# asset-tracker-v002.net
KiCad netlist of a schematic drawn in EAGLE
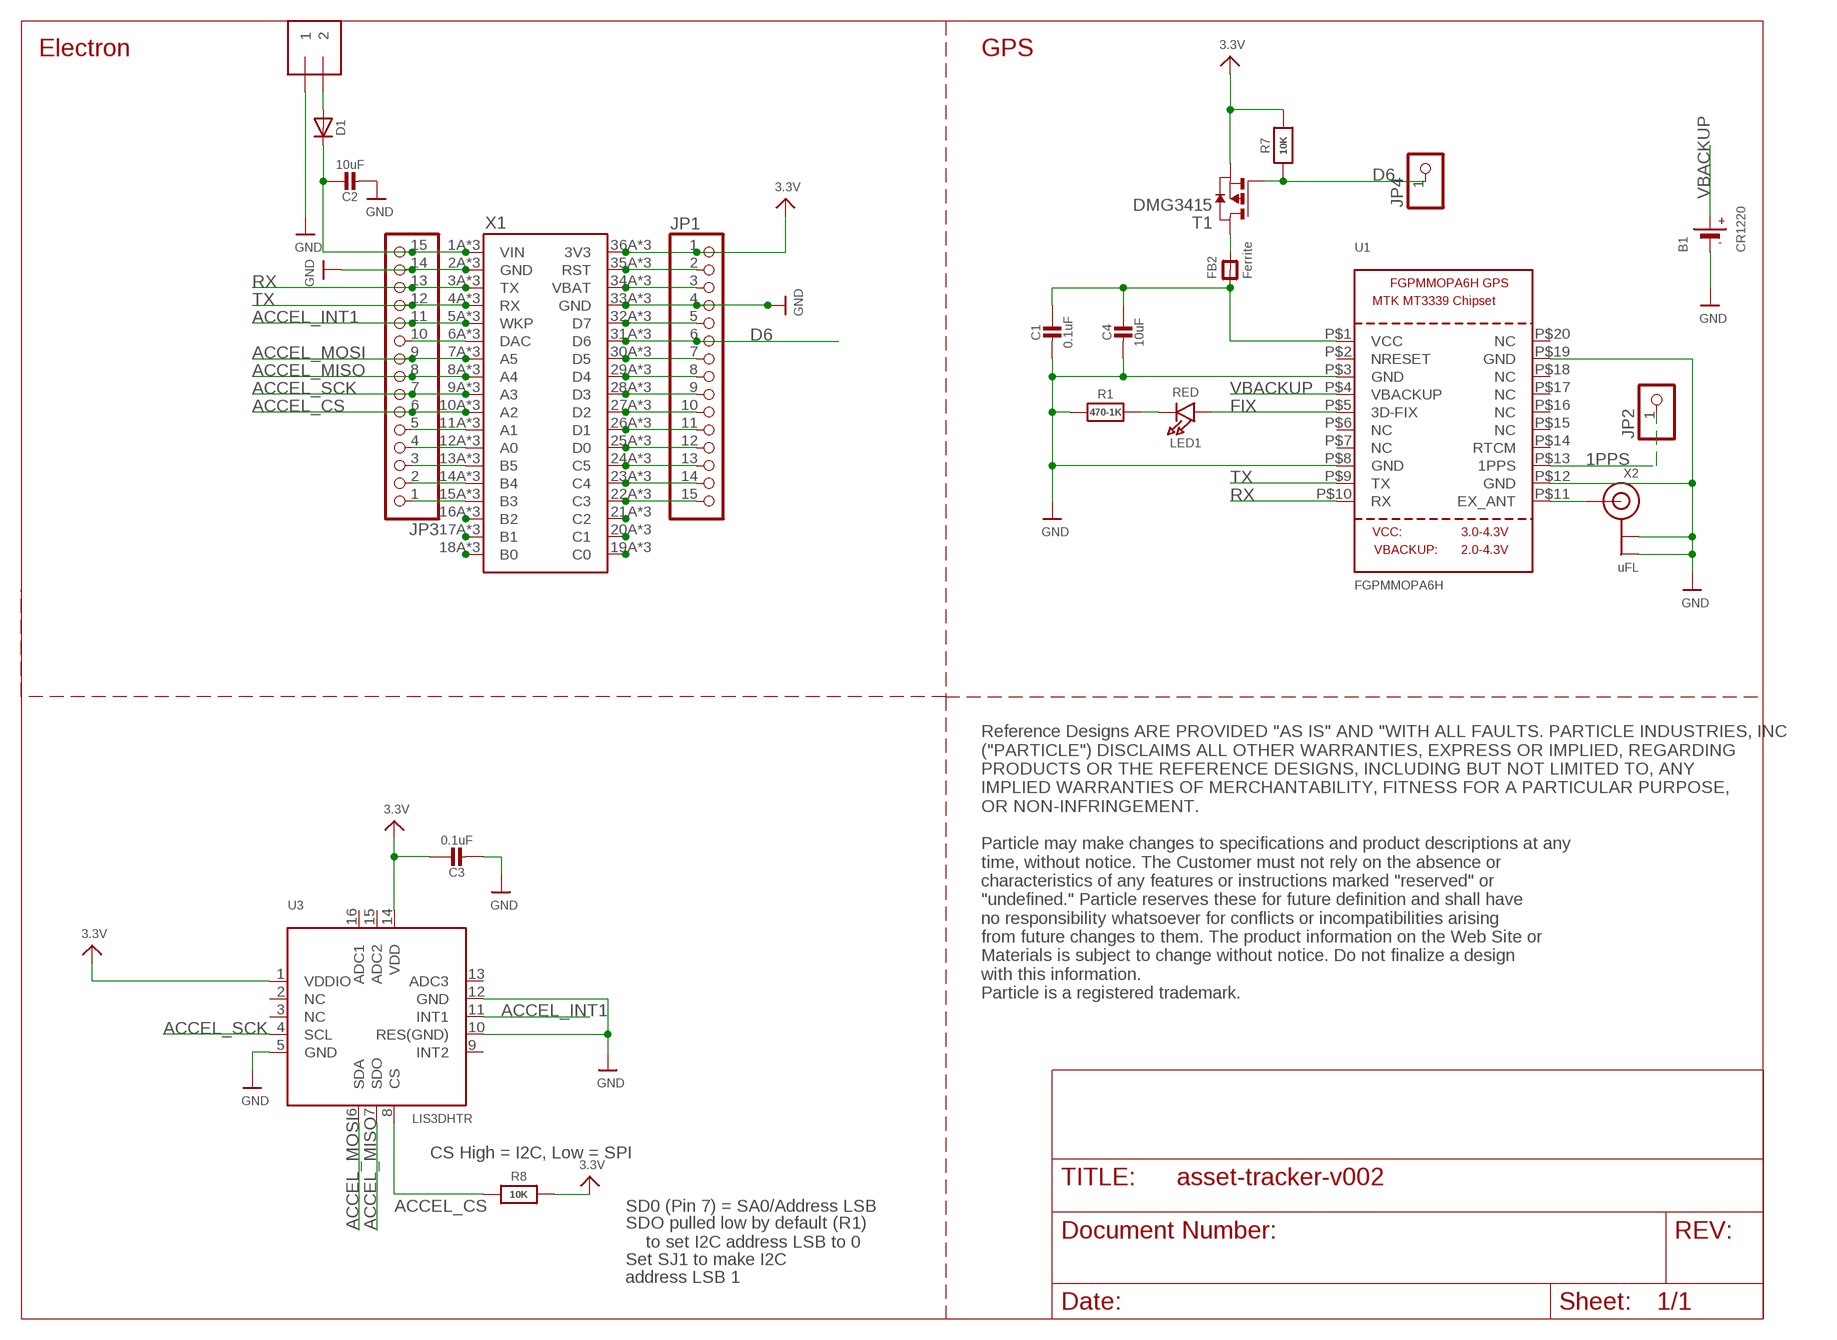
[diagram p0: schematic, sheet 1]

(export (version "E")
  (design (tool "Eeschema 10.0.6"))
  (components
    (comp (ref "B1")
      (value "CR1220")
      (footprint "eagle-import:CR1220")
      (libsource (lib "eagle-import") (part "BATTERYCR1220_SMT"))
    )
    (comp (ref "C1")
      (value "0.1uF")
      (footprint "eagle-import:0805-NO@1")
      (libsource (lib "eagle-import") (part "CAP_CERAMIC0805-NOOUTLINE"))
    )
    (comp (ref "C2")
      (value "10uF")
      (footprint "eagle-import:0805-NO@1")
      (libsource (lib "eagle-import") (part "CAP_CERAMIC0805-NOOUTLINE"))
    )
    (comp (ref "C3")
      (value "0.1uF")
      (footprint "eagle-import:0805_10MGAP")
      (libsource (lib "eagle-import") (part "CAP_CERAMIC0805_10MGAP"))
    )
    (comp (ref "C4")
      (value "10uF")
      (footprint "eagle-import:0805-NO@1")
      (libsource (lib "eagle-import") (part "CAP_CERAMIC0805-NOOUTLINE"))
    )
    (comp (ref "D1")
      (value "DIODESMA")
      (footprint "eagle-import:SMADIODE")
      (libsource (lib "eagle-import") (part "DIODESMA"))
    )
    (comp (ref "FB2")
      (value "Ferrite")
      (footprint "eagle-import:0805-NO@1")
      (libsource (lib "eagle-import") (part "FERRITE-0805NO"))
    )
    (comp (ref "J1")
      (value "1X2-3.5MM")
      (footprint "eagle-import:1X2-3.5MM")
      (libsource (lib "eagle-import") (part "1X2-3.5MM"))
    )
    (comp (ref "JP1")
      (value "HEADER-1X15")
      (footprint "eagle-import:1X15_ROUND_70")
      (libsource (lib "eagle-import") (part "HEADER-1X15"))
    )
    (comp (ref "JP2")
      (value "HEADER-1X1ROUND")
      (footprint "eagle-import:1X01_ROUND")
      (libsource (lib "eagle-import") (part "HEADER-1X1ROUND"))
    )
    (comp (ref "JP3")
      (value "HEADER-1X15")
      (footprint "eagle-import:1X15_ROUND_70")
      (libsource (lib "eagle-import") (part "HEADER-1X15"))
    )
    (comp (ref "JP4")
      (value "HEADER-1X1ROUND")
      (footprint "eagle-import:1X01_ROUND")
      (libsource (lib "eagle-import") (part "HEADER-1X1ROUND"))
    )
    (comp (ref "LED1")
      (value "RED")
      (footprint "eagle-import:CHIPLED_0805_NOOUTLINE")
      (libsource (lib "eagle-import") (part "LED0805_NOOUTLINE"))
    )
    (comp (ref "R1")
      (value "470-1K")
      (footprint "eagle-import:0805-NO")
      (libsource (lib "eagle-import") (part "RESISTOR0805_NOOUTLINE"))
    )
    (comp (ref "R7")
      (value "10K")
      (footprint "eagle-import:0805-NO")
      (libsource (lib "eagle-import") (part "RESISTOR0805_NOOUTLINE"))
    )
    (comp (ref "R8")
      (value "10K")
      (footprint "eagle-import:0805-NO")
      (libsource (lib "eagle-import") (part "RESISTOR0805_NOOUTLINE"))
    )
    (comp (ref "T1")
      (value "DMG3415")
      (footprint "eagle-import:SOT-23")
      (libsource (lib "eagle-import") (part "PMOSSOT23"))
    )
    (comp (ref "U1")
      (value "FGPMMOPA6H")
      (footprint "eagle-import:FGPMMOPA6H")
      (libsource (lib "eagle-import") (part "GPS_FGPMMOPA6H"))
    )
    (comp (ref "U3")
      (value "LIS3DHTR")
      (footprint "eagle-import:LGA16_3X3MM")
      (libsource (lib "eagle-import") (part "ACCEL_LIS3DHTR"))
    )
    (comp (ref "X1")
      (value "ELECTRON")
      (footprint "eagle-import:ELECTRON_SMT")
      (libsource (lib "eagle-import") (part "ELECTRON_SMT"))
    )
    (comp (ref "X2")
      (value "uFL")
      (footprint "eagle-import:U.FL")
      (libsource (lib "eagle-import") (part "ANTENNA_U.FL"))
    )
  )
  (nets
    (net (code "1") (name "/1PPS") (class "Default")
      (node (ref "JP2") (pin "1") (pinfunction "1_1") (pintype "passive"))
      (node (ref "U1") (pin "P$13") (pinfunction "1PPS_P$13") (pintype "bidirectional"))
    )
    (net (code "2") (name "/ACCEL_CS") (class "Default")
      (node (ref "JP3") (pin "6") (pinfunction "6_6") (pintype "passive"))
      (node (ref "R8") (pin "1") (pinfunction "1_1") (pintype "passive"))
      (node (ref "U3") (pin "8") (pinfunction "CS_8") (pintype "input"))
      (node (ref "X1") (pin "10A") (pinfunction "A2_10A") (pintype "bidirectional"))
      (node (ref "X1") (pin "10B") (pinfunction "A2_10B") (pintype "bidirectional"))
      (node (ref "X1") (pin "10C") (pinfunction "A2_10C") (pintype "bidirectional"))
    )
    (net (code "3") (name "/ACCEL_INT1") (class "Default")
      (node (ref "JP3") (pin "11") (pinfunction "11_11") (pintype "passive"))
      (node (ref "U3") (pin "11") (pinfunction "INT1_11") (pintype "output"))
      (node (ref "X1") (pin "5A") (pinfunction "WKP_5A") (pintype "bidirectional"))
      (node (ref "X1") (pin "5B") (pinfunction "WKP_5B") (pintype "bidirectional"))
      (node (ref "X1") (pin "5C") (pinfunction "WKP_5C") (pintype "bidirectional"))
    )
    (net (code "4") (name "/ACCEL_MISO") (class "Default")
      (node (ref "JP3") (pin "8") (pinfunction "8_8") (pintype "passive"))
      (node (ref "U3") (pin "7") (pinfunction "SDO_7") (pintype "bidirectional"))
      (node (ref "X1") (pin "8A") (pinfunction "A4_8A") (pintype "bidirectional"))
      (node (ref "X1") (pin "8B") (pinfunction "A4_8B") (pintype "bidirectional"))
      (node (ref "X1") (pin "8C") (pinfunction "A4_8C") (pintype "bidirectional"))
    )
    (net (code "5") (name "/ACCEL_MOSI") (class "Default")
      (node (ref "JP3") (pin "9") (pinfunction "9_9") (pintype "passive"))
      (node (ref "U3") (pin "6") (pinfunction "SDA_6") (pintype "bidirectional"))
      (node (ref "X1") (pin "7A") (pinfunction "A5_7A") (pintype "bidirectional"))
      (node (ref "X1") (pin "7B") (pinfunction "A5_7B") (pintype "bidirectional"))
      (node (ref "X1") (pin "7C") (pinfunction "A5_7C") (pintype "bidirectional"))
    )
    (net (code "6") (name "/ACCEL_SCK") (class "Default")
      (node (ref "JP3") (pin "7") (pinfunction "7_7") (pintype "passive"))
      (node (ref "U3") (pin "4") (pinfunction "SCL_4") (pintype "bidirectional"))
      (node (ref "X1") (pin "9A") (pinfunction "A3_9A") (pintype "bidirectional"))
      (node (ref "X1") (pin "9B") (pinfunction "A3_9B") (pintype "bidirectional"))
      (node (ref "X1") (pin "9C") (pinfunction "A3_9C") (pintype "bidirectional"))
    )
    (net (code "7") (name "/D6") (class "Default")
      (node (ref "JP1") (pin "6") (pinfunction "6_6") (pintype "passive"))
      (node (ref "JP4") (pin "1") (pinfunction "1_1") (pintype "passive"))
      (node (ref "R7") (pin "1") (pinfunction "1_1") (pintype "passive"))
      (node (ref "T1") (pin "3") (pinfunction "G_3") (pintype "passive"))
      (node (ref "X1") (pin "31A") (pinfunction "D6_31A") (pintype "bidirectional"))
      (node (ref "X1") (pin "31B") (pinfunction "D6_31B") (pintype "bidirectional"))
      (node (ref "X1") (pin "31C") (pinfunction "D6_31C") (pintype "bidirectional"))
    )
    (net (code "8") (name "/FIX") (class "Default")
      (node (ref "LED1") (pin "A") (pinfunction "A_A") (pintype "passive"))
      (node (ref "U1") (pin "P$5") (pinfunction "3D-FIX_P$5") (pintype "bidirectional"))
    )
    (net (code "9") (name "/RX") (class "Default")
      (node (ref "JP3") (pin "13") (pinfunction "13_13") (pintype "passive"))
      (node (ref "U1") (pin "P$10") (pinfunction "RX_P$10") (pintype "bidirectional"))
      (node (ref "X1") (pin "3A") (pinfunction "TX_3A") (pintype "bidirectional"))
      (node (ref "X1") (pin "3B") (pinfunction "TX_3B") (pintype "bidirectional"))
      (node (ref "X1") (pin "3C") (pinfunction "TX_3C") (pintype "bidirectional"))
    )
    (net (code "10") (name "/TX") (class "Default")
      (node (ref "JP3") (pin "12") (pinfunction "12_12") (pintype "passive"))
      (node (ref "U1") (pin "P$9") (pinfunction "TX_P$9") (pintype "bidirectional"))
      (node (ref "X1") (pin "4A") (pinfunction "RX_4A") (pintype "bidirectional"))
      (node (ref "X1") (pin "4B") (pinfunction "RX_4B") (pintype "bidirectional"))
      (node (ref "X1") (pin "4C") (pinfunction "RX_4C") (pintype "bidirectional"))
    )
    (net (code "11") (name "/VBACKUP") (class "Default")
      (node (ref "B1") (pin "+$1") (pinfunction "+_+$1") (pintype "passive"))
      (node (ref "U1") (pin "P$4") (pinfunction "VBACKUP_P$4") (pintype "bidirectional"))
    )
    (net (code "12") (name "3.3V") (class "Default")
      (node (ref "C3") (pin "1") (pinfunction "1_1") (pintype "passive"))
      (node (ref "JP1") (pin "1") (pinfunction "1_1") (pintype "passive"))
      (node (ref "R7") (pin "2") (pinfunction "2_2") (pintype "passive"))
      (node (ref "R8") (pin "2") (pinfunction "2_2") (pintype "passive"))
      (node (ref "T1") (pin "2") (pinfunction "S_2") (pintype "passive"))
      (node (ref "U3") (pin "1") (pinfunction "VDDIO_1") (pintype "power_in"))
      (node (ref "U3") (pin "14") (pinfunction "VDD_14") (pintype "power_in"))
      (node (ref "X1") (pin "36A") (pinfunction "3V3_36A") (pintype "power_in"))
      (node (ref "X1") (pin "36B") (pinfunction "3V3_36B") (pintype "power_in"))
      (node (ref "X1") (pin "36C") (pinfunction "3V3_36C") (pintype "power_in"))
    )
    (net (code "13") (name "GND") (class "Default")
      (node (ref "B1") (pin "-") (pinfunction "-_-") (pintype "passive"))
      (node (ref "C1") (pin "2") (pinfunction "2_2") (pintype "passive"))
      (node (ref "C2") (pin "2") (pinfunction "2_2") (pintype "passive"))
      (node (ref "C3") (pin "2") (pinfunction "2_2") (pintype "passive"))
      (node (ref "C4") (pin "2") (pinfunction "2_2") (pintype "passive"))
      (node (ref "J1") (pin "1") (pinfunction "1_1") (pintype "passive"))
      (node (ref "JP1") (pin "4") (pinfunction "4_4") (pintype "passive"))
      (node (ref "JP3") (pin "14") (pinfunction "14_14") (pintype "passive"))
      (node (ref "R1") (pin "1") (pinfunction "1_1") (pintype "passive"))
      (node (ref "U1") (pin "P$12") (pinfunction "GND_P$12") (pintype "bidirectional"))
      (node (ref "U1") (pin "P$19") (pinfunction "GND_P$19") (pintype "bidirectional"))
      (node (ref "U1") (pin "P$3") (pinfunction "GND_P$3") (pintype "bidirectional"))
      (node (ref "U1") (pin "P$8") (pinfunction "GND_P$8") (pintype "bidirectional"))
      (node (ref "U3") (pin "10") (pinfunction "RES(GND)_10") (pintype "bidirectional"))
      (node (ref "U3") (pin "12") (pinfunction "GND_12") (pintype "power_in"))
      (node (ref "U3") (pin "5") (pinfunction "GND_5") (pintype "power_in"))
      (node (ref "X1") (pin "2A") (pinfunction "GND_2A") (pintype "power_in"))
      (node (ref "X1") (pin "2B") (pinfunction "GND_2B") (pintype "power_in"))
      (node (ref "X1") (pin "2C") (pinfunction "GND_2C") (pintype "power_in"))
      (node (ref "X1") (pin "33A") (pinfunction "GND_33A") (pintype "power_in"))
      (node (ref "X1") (pin "33B") (pinfunction "GND_33B") (pintype "power_in"))
      (node (ref "X1") (pin "33C") (pinfunction "GND_33C") (pintype "power_in"))
      (node (ref "X2") (pin "1") (pinfunction "GND_1") (pintype "passive"))
      (node (ref "X2") (pin "2") (pinfunction "GND_2") (pintype "passive"))
    )
    (net (code "14") (name "Net-(C2-Pad1)") (class "Default")
      (node (ref "C2") (pin "1") (pinfunction "1_1") (pintype "passive"))
      (node (ref "D1") (pin "C") (pinfunction "C_C") (pintype "passive"))
      (node (ref "JP3") (pin "15") (pinfunction "15_15") (pintype "passive"))
      (node (ref "X1") (pin "1A") (pinfunction "VIN_1A") (pintype "power_in"))
      (node (ref "X1") (pin "1B") (pinfunction "VIN_1B") (pintype "power_in"))
      (node (ref "X1") (pin "1C") (pinfunction "VIN_1C") (pintype "power_in"))
    )
    (net (code "15") (name "Net-(D1-PadA)") (class "Default")
      (node (ref "D1") (pin "A") (pinfunction "A_A") (pintype "passive"))
      (node (ref "J1") (pin "2") (pinfunction "2_2") (pintype "passive"))
    )
    (net (code "16") (name "Net-(FB2-P$1)") (class "Default")
      (node (ref "C1") (pin "1") (pinfunction "1_1") (pintype "passive"))
      (node (ref "C4") (pin "1") (pinfunction "1_1") (pintype "passive"))
      (node (ref "FB2") (pin "1") (pinfunction "P$1_1") (pintype "passive"))
      (node (ref "U1") (pin "P$1") (pinfunction "VCC_P$1") (pintype "bidirectional"))
    )
    (net (code "17") (name "Net-(FB2-P$2)") (class "Default")
      (node (ref "FB2") (pin "2") (pinfunction "P$2_2") (pintype "passive"))
      (node (ref "T1") (pin "1") (pinfunction "D_1") (pintype "passive"))
    )
    (net (code "18") (name "Net-(JP1-Pad2)") (class "Default")
      (node (ref "JP1") (pin "2") (pinfunction "2_2") (pintype "passive"))
      (node (ref "X1") (pin "35A") (pinfunction "RST_35A") (pintype "bidirectional"))
      (node (ref "X1") (pin "35B") (pinfunction "RST_35B") (pintype "bidirectional"))
      (node (ref "X1") (pin "35C") (pinfunction "RST_35C") (pintype "bidirectional"))
    )
    (net (code "19") (name "Net-(JP1-Pad3)") (class "Default")
      (node (ref "JP1") (pin "3") (pinfunction "3_3") (pintype "passive"))
      (node (ref "X1") (pin "34A") (pinfunction "VBAT_34A") (pintype "passive"))
      (node (ref "X1") (pin "34B") (pinfunction "VBAT_34B") (pintype "passive"))
      (node (ref "X1") (pin "34C") (pinfunction "VBAT_34C") (pintype "passive"))
    )
    (net (code "20") (name "Net-(JP1-Pad5)") (class "Default")
      (node (ref "JP1") (pin "5") (pinfunction "5_5") (pintype "passive"))
      (node (ref "X1") (pin "32A") (pinfunction "D7_32A") (pintype "bidirectional"))
      (node (ref "X1") (pin "32B") (pinfunction "D7_32B") (pintype "bidirectional"))
      (node (ref "X1") (pin "32C") (pinfunction "D7_32C") (pintype "bidirectional"))
    )
    (net (code "21") (name "Net-(JP1-Pad7)") (class "Default")
      (node (ref "JP1") (pin "7") (pinfunction "7_7") (pintype "passive"))
      (node (ref "X1") (pin "30A") (pinfunction "D5_30A") (pintype "bidirectional"))
      (node (ref "X1") (pin "30B") (pinfunction "D5_30B") (pintype "bidirectional"))
      (node (ref "X1") (pin "30C") (pinfunction "D5_30C") (pintype "bidirectional"))
    )
    (net (code "22") (name "Net-(JP1-Pad8)") (class "Default")
      (node (ref "JP1") (pin "8") (pinfunction "8_8") (pintype "passive"))
      (node (ref "X1") (pin "29A") (pinfunction "D4_29A") (pintype "bidirectional"))
      (node (ref "X1") (pin "29B") (pinfunction "D4_29B") (pintype "bidirectional"))
      (node (ref "X1") (pin "29C") (pinfunction "D4_29C") (pintype "bidirectional"))
    )
    (net (code "23") (name "Net-(JP1-Pad9)") (class "Default")
      (node (ref "JP1") (pin "9") (pinfunction "9_9") (pintype "passive"))
      (node (ref "X1") (pin "28A") (pinfunction "D3_28A") (pintype "bidirectional"))
      (node (ref "X1") (pin "28B") (pinfunction "D3_28B") (pintype "bidirectional"))
      (node (ref "X1") (pin "28C") (pinfunction "D3_28C") (pintype "bidirectional"))
    )
    (net (code "24") (name "Net-(JP1-Pad10)") (class "Default")
      (node (ref "JP1") (pin "10") (pinfunction "10_10") (pintype "passive"))
      (node (ref "X1") (pin "27A") (pinfunction "D2_27A") (pintype "bidirectional"))
      (node (ref "X1") (pin "27B") (pinfunction "D2_27B") (pintype "bidirectional"))
      (node (ref "X1") (pin "27C") (pinfunction "D2_27C") (pintype "bidirectional"))
    )
    (net (code "25") (name "Net-(JP1-Pad11)") (class "Default")
      (node (ref "JP1") (pin "11") (pinfunction "11_11") (pintype "passive"))
      (node (ref "X1") (pin "26A") (pinfunction "D1_26A") (pintype "bidirectional"))
      (node (ref "X1") (pin "26B") (pinfunction "D1_26B") (pintype "bidirectional"))
      (node (ref "X1") (pin "26C") (pinfunction "D1_26C") (pintype "bidirectional"))
    )
    (net (code "26") (name "Net-(JP1-Pad12)") (class "Default")
      (node (ref "JP1") (pin "12") (pinfunction "12_12") (pintype "passive"))
      (node (ref "X1") (pin "25A") (pinfunction "D0_25A") (pintype "bidirectional"))
      (node (ref "X1") (pin "25B") (pinfunction "D0_25B") (pintype "bidirectional"))
      (node (ref "X1") (pin "25C") (pinfunction "D0_25C") (pintype "bidirectional"))
    )
    (net (code "27") (name "Net-(JP1-Pad13)") (class "Default")
      (node (ref "JP1") (pin "13") (pinfunction "13_13") (pintype "passive"))
      (node (ref "X1") (pin "24A") (pinfunction "C5_24A") (pintype "bidirectional"))
      (node (ref "X1") (pin "24B") (pinfunction "C5_24B") (pintype "bidirectional"))
      (node (ref "X1") (pin "24C") (pinfunction "C5_24C") (pintype "bidirectional"))
    )
    (net (code "28") (name "Net-(JP1-Pad14)") (class "Default")
      (node (ref "JP1") (pin "14") (pinfunction "14_14") (pintype "passive"))
      (node (ref "X1") (pin "23A") (pinfunction "C4_23A") (pintype "bidirectional"))
      (node (ref "X1") (pin "23B") (pinfunction "C4_23B") (pintype "bidirectional"))
      (node (ref "X1") (pin "23C") (pinfunction "C4_23C") (pintype "bidirectional"))
    )
    (net (code "29") (name "Net-(JP1-Pad15)") (class "Default")
      (node (ref "JP1") (pin "15") (pinfunction "15_15") (pintype "passive"))
      (node (ref "X1") (pin "22A") (pinfunction "C3_22A") (pintype "bidirectional"))
      (node (ref "X1") (pin "22B") (pinfunction "C3_22B") (pintype "bidirectional"))
      (node (ref "X1") (pin "22C") (pinfunction "C3_22C") (pintype "bidirectional"))
    )
    (net (code "30") (name "Net-(JP3-Pad1)") (class "Default")
      (node (ref "JP3") (pin "1") (pinfunction "1_1") (pintype "passive"))
      (node (ref "X1") (pin "15A") (pinfunction "B3_15A") (pintype "bidirectional"))
      (node (ref "X1") (pin "15B") (pinfunction "B3_15B") (pintype "bidirectional"))
      (node (ref "X1") (pin "15C") (pinfunction "B3_15C") (pintype "bidirectional"))
    )
    (net (code "31") (name "Net-(JP3-Pad2)") (class "Default")
      (node (ref "JP3") (pin "2") (pinfunction "2_2") (pintype "passive"))
      (node (ref "X1") (pin "14A") (pinfunction "B4_14A") (pintype "bidirectional"))
      (node (ref "X1") (pin "14B") (pinfunction "B4_14B") (pintype "bidirectional"))
      (node (ref "X1") (pin "14C") (pinfunction "B4_14C") (pintype "bidirectional"))
    )
    (net (code "32") (name "Net-(JP3-Pad3)") (class "Default")
      (node (ref "JP3") (pin "3") (pinfunction "3_3") (pintype "passive"))
      (node (ref "X1") (pin "13A") (pinfunction "B5_13A") (pintype "bidirectional"))
      (node (ref "X1") (pin "13B") (pinfunction "B5_13B") (pintype "bidirectional"))
      (node (ref "X1") (pin "13C") (pinfunction "B5_13C") (pintype "bidirectional"))
    )
    (net (code "33") (name "Net-(JP3-Pad4)") (class "Default")
      (node (ref "JP3") (pin "4") (pinfunction "4_4") (pintype "passive"))
      (node (ref "X1") (pin "12A") (pinfunction "A0_12A") (pintype "bidirectional"))
      (node (ref "X1") (pin "12B") (pinfunction "A0_12B") (pintype "bidirectional"))
      (node (ref "X1") (pin "12C") (pinfunction "A0_12C") (pintype "bidirectional"))
    )
    (net (code "34") (name "Net-(JP3-Pad5)") (class "Default")
      (node (ref "JP3") (pin "5") (pinfunction "5_5") (pintype "passive"))
      (node (ref "X1") (pin "11A") (pinfunction "A1_11A") (pintype "bidirectional"))
      (node (ref "X1") (pin "11B") (pinfunction "A1_11B") (pintype "bidirectional"))
      (node (ref "X1") (pin "11C") (pinfunction "A1_11C") (pintype "bidirectional"))
    )
    (net (code "35") (name "Net-(JP3-Pad10)") (class "Default")
      (node (ref "JP3") (pin "10") (pinfunction "10_10") (pintype "passive"))
      (node (ref "X1") (pin "6A") (pinfunction "DAC_6A") (pintype "bidirectional"))
      (node (ref "X1") (pin "6B") (pinfunction "DAC_6B") (pintype "bidirectional"))
      (node (ref "X1") (pin "6C") (pinfunction "DAC_6C") (pintype "bidirectional"))
    )
    (net (code "36") (name "Net-(LED1-PadC)") (class "Default")
      (node (ref "LED1") (pin "C") (pinfunction "C_C") (pintype "passive"))
      (node (ref "R1") (pin "2") (pinfunction "2_2") (pintype "passive"))
    )
    (net (code "37") (name "Net-(U1-EX_ANT)") (class "Default")
      (node (ref "U1") (pin "P$11") (pinfunction "EX_ANT_P$11") (pintype "bidirectional"))
      (node (ref "X2") (pin "3") (pinfunction "SIGNAL_3") (pintype "passive"))
    )
    (net (code "38") (name "Net-(X1-B0-Pad18A)") (class "Default")
      (node (ref "X1") (pin "18A") (pinfunction "B0_18A") (pintype "bidirectional"))
      (node (ref "X1") (pin "18B") (pinfunction "B0_18B") (pintype "bidirectional"))
      (node (ref "X1") (pin "18C") (pinfunction "B0_18C") (pintype "bidirectional"))
    )
    (net (code "39") (name "Net-(X1-B1-Pad17A)") (class "Default")
      (node (ref "X1") (pin "17A") (pinfunction "B1_17A") (pintype "bidirectional"))
      (node (ref "X1") (pin "17B") (pinfunction "B1_17B") (pintype "bidirectional"))
      (node (ref "X1") (pin "17C") (pinfunction "B1_17C") (pintype "bidirectional"))
    )
    (net (code "40") (name "Net-(X1-B2-Pad16A)") (class "Default")
      (node (ref "X1") (pin "16A") (pinfunction "B2_16A") (pintype "bidirectional"))
      (node (ref "X1") (pin "16B") (pinfunction "B2_16B") (pintype "bidirectional"))
      (node (ref "X1") (pin "16C") (pinfunction "B2_16C") (pintype "bidirectional"))
    )
    (net (code "41") (name "Net-(X1-C0-Pad19A)") (class "Default")
      (node (ref "X1") (pin "19A") (pinfunction "C0_19A") (pintype "bidirectional"))
      (node (ref "X1") (pin "19B") (pinfunction "C0_19B") (pintype "bidirectional"))
      (node (ref "X1") (pin "19C") (pinfunction "C0_19C") (pintype "bidirectional"))
    )
    (net (code "42") (name "Net-(X1-C1-Pad20A)") (class "Default")
      (node (ref "X1") (pin "20A") (pinfunction "C1_20A") (pintype "bidirectional"))
      (node (ref "X1") (pin "20B") (pinfunction "C1_20B") (pintype "bidirectional"))
      (node (ref "X1") (pin "20C") (pinfunction "C1_20C") (pintype "bidirectional"))
    )
    (net (code "43") (name "Net-(X1-C2-Pad21A)") (class "Default")
      (node (ref "X1") (pin "21A") (pinfunction "C2_21A") (pintype "bidirectional"))
      (node (ref "X1") (pin "21B") (pinfunction "C2_21B") (pintype "bidirectional"))
      (node (ref "X1") (pin "21C") (pinfunction "C2_21C") (pintype "bidirectional"))
    )
    (net (code "44") (name "unconnected-(U1-NC-PadP$6)") (class "Default")
      (node (ref "U1") (pin "P$6") (pinfunction "NC_P$6") (pintype "bidirectional"))
    )
    (net (code "45") (name "unconnected-(U1-NC-PadP$7)") (class "Default")
      (node (ref "U1") (pin "P$7") (pinfunction "NC_P$7") (pintype "bidirectional"))
    )
    (net (code "46") (name "unconnected-(U1-NC-PadP$15)") (class "Default")
      (node (ref "U1") (pin "P$15") (pinfunction "NC_P$15") (pintype "bidirectional"))
    )
    (net (code "47") (name "unconnected-(U1-NC-PadP$16)") (class "Default")
      (node (ref "U1") (pin "P$16") (pinfunction "NC_P$16") (pintype "bidirectional"))
    )
    (net (code "48") (name "unconnected-(U1-NC-PadP$17)") (class "Default")
      (node (ref "U1") (pin "P$17") (pinfunction "NC_P$17") (pintype "bidirectional"))
    )
    (net (code "49") (name "unconnected-(U1-NC-PadP$18)") (class "Default")
      (node (ref "U1") (pin "P$18") (pinfunction "NC_P$18") (pintype "bidirectional"))
    )
    (net (code "50") (name "unconnected-(U1-NC-PadP$20)") (class "Default")
      (node (ref "U1") (pin "P$20") (pinfunction "NC_P$20") (pintype "bidirectional"))
    )
    (net (code "51") (name "unconnected-(U1-NRESET-PadP$2)") (class "Default")
      (node (ref "U1") (pin "P$2") (pinfunction "NRESET_P$2") (pintype "bidirectional"))
    )
    (net (code "52") (name "unconnected-(U1-RTCM-PadP$14)") (class "Default")
      (node (ref "U1") (pin "P$14") (pinfunction "RTCM_P$14") (pintype "bidirectional"))
    )
    (net (code "53") (name "unconnected-(U3-ADC1-Pad16)") (class "Default")
      (node (ref "U3") (pin "16") (pinfunction "ADC1_16") (pintype "input"))
    )
    (net (code "54") (name "unconnected-(U3-ADC2-Pad15)") (class "Default")
      (node (ref "U3") (pin "15") (pinfunction "ADC2_15") (pintype "input"))
    )
    (net (code "55") (name "unconnected-(U3-ADC3-Pad13)") (class "Default")
      (node (ref "U3") (pin "13") (pinfunction "ADC3_13") (pintype "input"))
    )
    (net (code "56") (name "unconnected-(U3-INT2-Pad9)") (class "Default")
      (node (ref "U3") (pin "9") (pinfunction "INT2_9") (pintype "output"))
    )
    (net (code "57") (name "unconnected-(U3-NC-Pad2)") (class "Default")
      (node (ref "U3") (pin "2") (pinfunction "NC_2") (pintype "no_connect"))
    )
    (net (code "58") (name "unconnected-(U3-NC-Pad3)") (class "Default")
      (node (ref "U3") (pin "3") (pinfunction "NC_3") (pintype "no_connect"))
    )
  )
)
